# BLDC_driver_sensorless_logic.net
KiCad netlist of a schematic drawn in Altium Designer
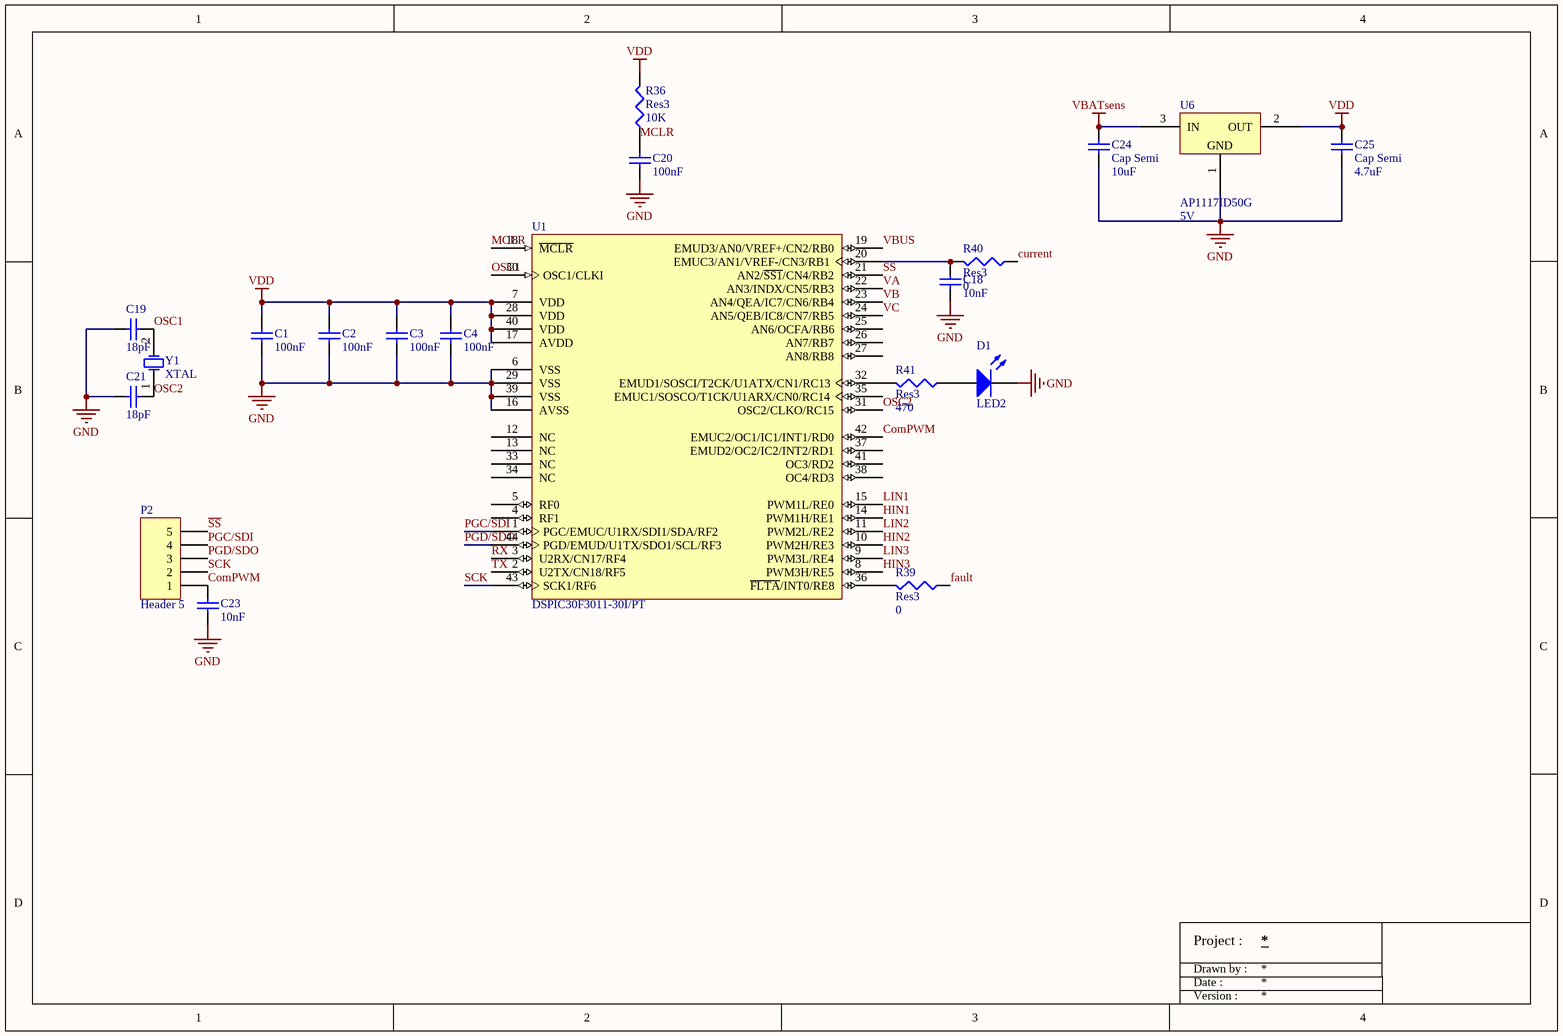
[diagram p0: BLDC_driver_sensorless_logic.SchDoc]

(export (version "E")
  (design (tool "Eeschema 10.0.6"))
  (components
    (comp (ref "C1")
      (value "100nF")
      (footprint "1206 capacitor")
      (description "SMD capacitor")
      (fields (field (name "Comment") "Cap SMD"))
      (libsource (lib "Miscellaneous Devices") (part "Cap SMD"))
    )
    (comp (ref "C2")
      (value "100nF")
      (footprint "1206 capacitor")
      (description "SMD capacitor")
      (fields (field (name "Comment") "Cap SMD"))
      (libsource (lib "Miscellaneous Devices") (part "Cap SMD"))
    )
    (comp (ref "C3")
      (value "100nF")
      (footprint "1206 capacitor")
      (description "SMD capacitor")
      (fields (field (name "Comment") "Cap SMD"))
      (libsource (lib "Miscellaneous Devices") (part "Cap SMD"))
    )
    (comp (ref "C4")
      (value "100nF")
      (footprint "1206 capacitor")
      (description "SMD capacitor")
      (fields (field (name "Comment") "Cap SMD"))
      (libsource (lib "Miscellaneous Devices") (part "Cap SMD"))
    )
    (comp (ref "C18")
      (value "10nF")
      (footprint "1206 capacitor")
      (description "SMD capacitor")
      (fields (field (name "Comment") "Cap SMD"))
      (libsource (lib "Miscellaneous Devices") (part "Cap SMD"))
    )
    (comp (ref "C19")
      (value "18pF")
      (footprint "1206 capacitor")
      (description "SMD capacitor")
      (fields (field (name "Comment") "Cap SMD"))
      (libsource (lib "Miscellaneous Devices") (part "Cap SMD"))
    )
    (comp (ref "C20")
      (value "100nF")
      (footprint "1206 capacitor")
      (description "SMD capacitor")
      (fields (field (name "Comment") "Cap SMD"))
      (libsource (lib "Miscellaneous Devices") (part "Cap SMD"))
    )
    (comp (ref "C21")
      (value "18pF")
      (footprint "1206 capacitor")
      (description "SMD capacitor")
      (fields (field (name "Comment") "Cap SMD"))
      (libsource (lib "Miscellaneous Devices") (part "Cap SMD"))
    )
    (comp (ref "C23")
      (value "10nF")
      (footprint "1206 capacitor")
      (description "SMD capacitor")
      (fields (field (name "Comment") "Cap SMD"))
      (libsource (lib "Miscellaneous Devices") (part "Cap SMD"))
    )
    (comp (ref "C24")
      (value "Cap Semi")
      (footprint "1206 capacitor")
      (description "Capacitor (Semiconductor SIM Model)")
      (fields (field (name "ALTIUM_VALUE") "10uF") (field (name "PUBLISHER") "Altium Limited"))
      (libsource (lib "Miscellaneous Devices") (part "Cap Semi"))
    )
    (comp (ref "C25")
      (value "Cap Semi")
      (footprint "1206 capacitor")
      (description "Capacitor (Semiconductor SIM Model)")
      (fields (field (name "ALTIUM_VALUE") "4.7uF") (field (name "PUBLISHER") "Altium Limited"))
      (libsource (lib "Miscellaneous Devices") (part "Cap Semi"))
    )
    (comp (ref "D1")
      (value "LED2")
      (footprint "LED 1206 BLUE")
      (description "Typical RED, GREEN, YELLOW, AMBER GaAs LED")
      (fields (field (name "PUBLISHER") "Altium Limited"))
      (libsource (lib "Miscellaneous Devices") (part "LED2"))
    )
    (comp (ref "P2")
      (value "Header 5")
      (footprint "HDR1X5")
      (description "Header, 5-Pin")
      (fields (field (name "PUBLISHER") "Altium Limited"))
      (libsource (lib "Miscellaneous Connectors") (part "Header 5"))
    )
    (comp (ref "R36")
      (value "Res3")
      (footprint "1206 resistor")
      (description "Resistor")
      (fields (field (name "ALTIUM_VALUE") "10K") (field (name "PUBLISHER") "Altium Limited"))
      (libsource (lib "Miscellaneous Devices") (part "Res3"))
    )
    (comp (ref "R39")
      (value "Res3")
      (footprint "1206 resistor")
      (description "Resistor")
      (fields (field (name "ALTIUM_VALUE") "0") (field (name "PUBLISHER") "Altium Limited"))
      (libsource (lib "Miscellaneous Devices") (part "Res3"))
    )
    (comp (ref "R40")
      (value "Res3")
      (footprint "1206 resistor")
      (description "Resistor")
      (fields (field (name "ALTIUM_VALUE") "0") (field (name "PUBLISHER") "Altium Limited"))
      (libsource (lib "Miscellaneous Devices") (part "Res3"))
    )
    (comp (ref "R41")
      (value "Res3")
      (footprint "1206 resistor")
      (description "Resistor")
      (fields (field (name "ALTIUM_VALUE") "470") (field (name "PUBLISHER") "Altium Limited"))
      (libsource (lib "Miscellaneous Devices") (part "Res3"))
    )
    (comp (ref "U1")
      (value "DSPIC30F3011-30I/PT")
      (footprint "TQFP-PT44_N")
      (fields (field (name "PUBLISHER") "Altium Limited"))
      (libsource (lib "Microchip DSC 16-Bit dsPIC30F") (part "DSPIC30F3011-30I/PT"))
    )
    (comp (ref "U6")
      (value "AP1117ID50G")
      (footprint "TO-252")
      (description "LDO Voltage Regulator")
      (fields (field (name "ALTIUM_VALUE") "5V") (field (name "PUBLISHER") "Altium Limited"))
      (libsource (lib "Miscellaneous Devices 2") (part "AP1117ID50G"))
    )
    (comp (ref "Y1")
      (value "XTAL")
      (footprint "HC49/US")
      (description "Crystal Oscillator")
      (fields (field (name "PUBLISHER") "Altium Limited"))
      (libsource (lib "Miscellaneous Devices") (part "XTAL"))
    )
  )
  (nets
    (net (code "1") (name "/ComPWM") (class "Default")
      (node (ref "C23") (pin "2") (pinfunction "2_2") (pintype "passive"))
      (node (ref "P2") (pin "1") (pinfunction "1_1") (pintype "passive"))
      (node (ref "U1") (pin "42") (pinfunction "EMUC2/OC1/IC1/INT1/RD0_42") (pintype "bidirectional"))
    )
    (net (code "2") (name "/HIN1") (class "Default")
      (node (ref "U1") (pin "14") (pinfunction "PWM1H/RE1_14") (pintype "bidirectional"))
    )
    (net (code "3") (name "/HIN2") (class "Default")
      (node (ref "U1") (pin "10") (pinfunction "PWM2H/RE3_10") (pintype "bidirectional"))
    )
    (net (code "4") (name "/HIN3") (class "Default")
      (node (ref "U1") (pin "8") (pinfunction "PWM3H/RE5_8") (pintype "bidirectional"))
    )
    (net (code "5") (name "/LIN1") (class "Default")
      (node (ref "U1") (pin "15") (pinfunction "PWM1L/RE0_15") (pintype "bidirectional"))
    )
    (net (code "6") (name "/LIN2") (class "Default")
      (node (ref "U1") (pin "11") (pinfunction "PWM2L/RE2_11") (pintype "bidirectional"))
    )
    (net (code "7") (name "/LIN3") (class "Default")
      (node (ref "U1") (pin "9") (pinfunction "PWM3L/RE4_9") (pintype "bidirectional"))
    )
    (net (code "8") (name "/MCLR") (class "Default")
      (node (ref "C20") (pin "2") (pinfunction "2_2") (pintype "passive"))
      (node (ref "R36") (pin "1") (pinfunction "1_1") (pintype "passive"))
      (node (ref "U1") (pin "18") (pinfunction "~{MCLR}_18") (pintype "input"))
    )
    (net (code "9") (name "/OSC1") (class "Default")
      (node (ref "C19") (pin "1") (pinfunction "1_1") (pintype "passive"))
      (node (ref "U1") (pin "30") (pinfunction "OSC1/CLKI_30") (pintype "input"))
      (node (ref "Y1") (pin "2") (pinfunction "OSC2_2") (pintype "passive"))
    )
    (net (code "10") (name "/OSC2") (class "Default")
      (node (ref "C21") (pin "1") (pinfunction "1_1") (pintype "passive"))
      (node (ref "U1") (pin "31") (pinfunction "OSC2/CLKO/RC15_31") (pintype "bidirectional"))
      (node (ref "Y1") (pin "1") (pinfunction "OSC1_1") (pintype "passive"))
    )
    (net (code "11") (name "/PGC{slash}SDI") (class "Default")
      (node (ref "P2") (pin "4") (pinfunction "4_4") (pintype "passive"))
      (node (ref "U1") (pin "1") (pinfunction "PGC/EMUC/U1RX/SDI1/SDA/RF2_1") (pintype "bidirectional"))
    )
    (net (code "12") (name "/PGD{slash}SDO") (class "Default")
      (node (ref "P2") (pin "3") (pinfunction "3_3") (pintype "passive"))
      (node (ref "U1") (pin "44") (pinfunction "PGD/EMUD/U1TX/SDO1/SCL/RF3_44") (pintype "bidirectional"))
    )
    (net (code "13") (name "/RX") (class "Default")
      (node (ref "U1") (pin "3") (pinfunction "U2RX/CN17/RF4_3") (pintype "bidirectional"))
    )
    (net (code "14") (name "/SCK") (class "Default")
      (node (ref "P2") (pin "2") (pinfunction "2_2") (pintype "passive"))
      (node (ref "U1") (pin "43") (pinfunction "SCK1/RF6_43") (pintype "bidirectional"))
    )
    (net (code "15") (name "/TX") (class "Default")
      (node (ref "U1") (pin "2") (pinfunction "U2TX/CN18/RF5_2") (pintype "bidirectional"))
    )
    (net (code "16") (name "/VA") (class "Default")
      (node (ref "U1") (pin "22") (pinfunction "AN3/INDX/CN5/RB3_22") (pintype "bidirectional"))
    )
    (net (code "17") (name "/VB") (class "Default")
      (node (ref "U1") (pin "23") (pinfunction "AN4/QEA/IC7/CN6/RB4_23") (pintype "bidirectional"))
    )
    (net (code "18") (name "/VBUS") (class "Default")
      (node (ref "U1") (pin "19") (pinfunction "EMUD3/AN0/VREF+/CN2/RB0_19") (pintype "bidirectional"))
    )
    (net (code "19") (name "/VC") (class "Default")
      (node (ref "U1") (pin "24") (pinfunction "AN5/QEB/IC8/CN7/RB5_24") (pintype "bidirectional"))
    )
    (net (code "20") (name "/current") (class "Default")
      (node (ref "R40") (pin "1") (pinfunction "1_1") (pintype "passive"))
    )
    (net (code "21") (name "/fault") (class "Default")
      (node (ref "R39") (pin "1") (pinfunction "1_1") (pintype "passive"))
    )
    (net (code "22") (name "/~{SS}") (class "Default")
      (node (ref "P2") (pin "5") (pinfunction "5_5") (pintype "passive"))
      (node (ref "U1") (pin "21") (pinfunction "AN2/~{SS1}/CN4/RB2_21") (pintype "bidirectional"))
    )
    (net (code "23") (name "GND") (class "Default")
      (node (ref "C1") (pin "1") (pinfunction "1_1") (pintype "passive"))
      (node (ref "C18") (pin "1") (pinfunction "1_1") (pintype "passive"))
      (node (ref "C19") (pin "2") (pinfunction "2_2") (pintype "passive"))
      (node (ref "C2") (pin "1") (pinfunction "1_1") (pintype "passive"))
      (node (ref "C20") (pin "1") (pinfunction "1_1") (pintype "passive"))
      (node (ref "C21") (pin "2") (pinfunction "2_2") (pintype "passive"))
      (node (ref "C23") (pin "1") (pinfunction "1_1") (pintype "passive"))
      (node (ref "C24") (pin "1") (pinfunction "1_1") (pintype "passive"))
      (node (ref "C25") (pin "1") (pinfunction "1_1") (pintype "passive"))
      (node (ref "C3") (pin "1") (pinfunction "1_1") (pintype "passive"))
      (node (ref "C4") (pin "1") (pinfunction "1_1") (pintype "passive"))
      (node (ref "D1") (pin "2") (pinfunction "K_2") (pintype "passive"))
      (node (ref "U1") (pin "16") (pinfunction "AVSS_16") (pintype "power_in"))
      (node (ref "U1") (pin "29") (pinfunction "VSS_29") (pintype "power_in"))
      (node (ref "U1") (pin "39") (pinfunction "VSS_39") (pintype "power_in"))
      (node (ref "U1") (pin "6") (pinfunction "VSS_6") (pintype "power_in"))
      (node (ref "U6") (pin "1") (pinfunction "GND_1") (pintype "passive"))
    )
    (net (code "24") (name "Net-(D1-A)") (class "Default")
      (node (ref "D1") (pin "1") (pinfunction "A_1") (pintype "passive"))
      (node (ref "R41") (pin "1") (pinfunction "1_1") (pintype "passive"))
    )
    (net (code "25") (name "Net-(U1-EMUC3{slash}AN1{slash}VREF-{slash}CN3{slash}RB1)") (class "Default")
      (node (ref "C18") (pin "2") (pinfunction "2_2") (pintype "passive"))
      (node (ref "R40") (pin "2") (pinfunction "2_2") (pintype "passive"))
      (node (ref "U1") (pin "20") (pinfunction "EMUC3/AN1/VREF-/CN3/RB1_20") (pintype "bidirectional"))
    )
    (net (code "26") (name "Net-(U1-EMUD1{slash}SOSCI{slash}T2CK{slash}U1ATX{slash}CN1{slash}RC13)") (class "Default")
      (node (ref "R41") (pin "2") (pinfunction "2_2") (pintype "passive"))
      (node (ref "U1") (pin "32") (pinfunction "EMUD1/SOSCI/T2CK/U1ATX/CN1/RC13_32") (pintype "bidirectional"))
    )
    (net (code "27") (name "Net-(U1-~{FLTA}{slash}INT0{slash}RE8)") (class "Default")
      (node (ref "R39") (pin "2") (pinfunction "2_2") (pintype "passive"))
      (node (ref "U1") (pin "36") (pinfunction "~{FLTA}/INT0/RE8_36") (pintype "bidirectional"))
    )
    (net (code "28") (name "VBATsens") (class "Default")
      (node (ref "C24") (pin "2") (pinfunction "2_2") (pintype "passive"))
      (node (ref "U6") (pin "3") (pinfunction "IN_3") (pintype "passive"))
    )
    (net (code "29") (name "VDD") (class "Default")
      (node (ref "C1") (pin "2") (pinfunction "2_2") (pintype "passive"))
      (node (ref "C2") (pin "2") (pinfunction "2_2") (pintype "passive"))
      (node (ref "C25") (pin "2") (pinfunction "2_2") (pintype "passive"))
      (node (ref "C3") (pin "2") (pinfunction "2_2") (pintype "passive"))
      (node (ref "C4") (pin "2") (pinfunction "2_2") (pintype "passive"))
      (node (ref "R36") (pin "2") (pinfunction "2_2") (pintype "passive"))
      (node (ref "U1") (pin "17") (pinfunction "AVDD_17") (pintype "power_in"))
      (node (ref "U1") (pin "28") (pinfunction "VDD_28") (pintype "power_in"))
      (node (ref "U1") (pin "40") (pinfunction "VDD_40") (pintype "power_in"))
      (node (ref "U1") (pin "7") (pinfunction "VDD_7") (pintype "power_in"))
      (node (ref "U6") (pin "2") (pinfunction "OUT_2") (pintype "passive"))
    )
    (net (code "30") (name "unconnected-(U1-AN6{slash}OCFA{slash}RB6-Pad25)") (class "Default")
      (node (ref "U1") (pin "25") (pinfunction "AN6/OCFA/RB6_25") (pintype "bidirectional"))
    )
    (net (code "31") (name "unconnected-(U1-AN7{slash}RB7-Pad26)") (class "Default")
      (node (ref "U1") (pin "26") (pinfunction "AN7/RB7_26") (pintype "bidirectional"))
    )
    (net (code "32") (name "unconnected-(U1-AN8{slash}RB8-Pad27)") (class "Default")
      (node (ref "U1") (pin "27") (pinfunction "AN8/RB8_27") (pintype "bidirectional"))
    )
    (net (code "33") (name "unconnected-(U1-EMUC1{slash}SOSCO{slash}T1CK{slash}U1ARX{slash}CN0{slash}RC14-Pad35)") (class "Default")
      (node (ref "U1") (pin "35") (pinfunction "EMUC1/SOSCO/T1CK/U1ARX/CN0/RC14_35") (pintype "bidirectional"))
    )
    (net (code "34") (name "unconnected-(U1-EMUD2{slash}OC2{slash}IC2{slash}INT2{slash}RD1-Pad37)") (class "Default")
      (node (ref "U1") (pin "37") (pinfunction "EMUD2/OC2/IC2/INT2/RD1_37") (pintype "bidirectional"))
    )
    (net (code "35") (name "unconnected-(U1-NC-Pad12)") (class "Default")
      (node (ref "U1") (pin "12") (pinfunction "NC_12") (pintype "passive"))
    )
    (net (code "36") (name "unconnected-(U1-NC-Pad13)") (class "Default")
      (node (ref "U1") (pin "13") (pinfunction "NC_13") (pintype "passive"))
    )
    (net (code "37") (name "unconnected-(U1-NC-Pad33)") (class "Default")
      (node (ref "U1") (pin "33") (pinfunction "NC_33") (pintype "passive"))
    )
    (net (code "38") (name "unconnected-(U1-NC-Pad34)") (class "Default")
      (node (ref "U1") (pin "34") (pinfunction "NC_34") (pintype "passive"))
    )
    (net (code "39") (name "unconnected-(U1-OC3{slash}RD2-Pad41)") (class "Default")
      (node (ref "U1") (pin "41") (pinfunction "OC3/RD2_41") (pintype "bidirectional"))
    )
    (net (code "40") (name "unconnected-(U1-OC4{slash}RD3-Pad38)") (class "Default")
      (node (ref "U1") (pin "38") (pinfunction "OC4/RD3_38") (pintype "bidirectional"))
    )
    (net (code "41") (name "unconnected-(U1-RF0-Pad5)") (class "Default")
      (node (ref "U1") (pin "5") (pinfunction "RF0_5") (pintype "bidirectional"))
    )
    (net (code "42") (name "unconnected-(U1-RF1-Pad4)") (class "Default")
      (node (ref "U1") (pin "4") (pinfunction "RF1_4") (pintype "bidirectional"))
    )
  )
)
